# Zvukovuha2.net
KiCad netlist of a schematic drawn in EAGLE
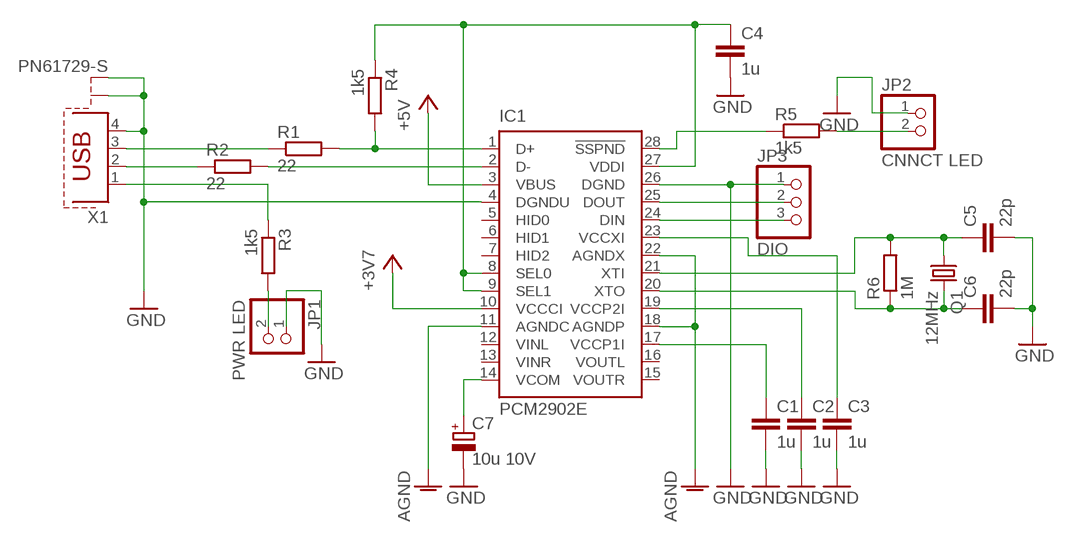
[diagram p0: schematic, sheet 1]

(export (version "E")
  (design (tool "Eeschema 10.0.6"))
  (components
    (comp (ref "C1")
      (value "1u")
      (footprint "eagle-import:C0805")
      (libsource (lib "eagle-import") (part "C-EUC0805"))
    )
    (comp (ref "C2")
      (value "1u")
      (footprint "eagle-import:C0805")
      (libsource (lib "eagle-import") (part "C-EUC0805"))
    )
    (comp (ref "C3")
      (value "1u")
      (footprint "eagle-import:C0805")
      (libsource (lib "eagle-import") (part "C-EUC0805"))
    )
    (comp (ref "C4")
      (value "1u")
      (footprint "eagle-import:C0805")
      (libsource (lib "eagle-import") (part "C-EUC0805"))
    )
    (comp (ref "C5")
      (value "22p")
      (footprint "eagle-import:C0805")
      (libsource (lib "eagle-import") (part "C-EUC0805"))
    )
    (comp (ref "C6")
      (value "22p")
      (footprint "eagle-import:C0805")
      (libsource (lib "eagle-import") (part "C-EUC0805"))
    )
    (comp (ref "C7")
      (value "10u 10V")
      (footprint "eagle-import:UD-6,3X7,7_NICHICON")
      (libsource (lib "eagle-import") (part "CPOL-EUUD-6,3X7,7"))
    )
    (comp (ref "IC1")
      (value "PCM2902E")
      (footprint "eagle-import:SSOP28DB")
      (fields (field (name "MF") "TEXAS INSTRUMENT CONNECTORS"))
      (libsource (lib "eagle-import") (part "PCM2902E"))
    )
    (comp (ref "JP1")
      (value "PWR LED")
      (footprint "eagle-import:1X02")
      (libsource (lib "eagle-import") (part "PINHD-1X2"))
    )
    (comp (ref "JP2")
      (value "CNNCT LED")
      (footprint "eagle-import:1X02")
      (libsource (lib "eagle-import") (part "PINHD-1X2"))
    )
    (comp (ref "JP3")
      (value "DIO")
      (footprint "eagle-import:1X03")
      (libsource (lib "eagle-import") (part "PINHD-1X3"))
    )
    (comp (ref "Q1")
      (value "12MHz")
      (footprint "eagle-import:CSM-7X-DU")
      (libsource (lib "eagle-import") (part "CSM-7X-DU"))
    )
    (comp (ref "R1")
      (value "22")
      (footprint "eagle-import:M1206")
      (libsource (lib "eagle-import") (part "R-EU_M1206"))
    )
    (comp (ref "R2")
      (value "22")
      (footprint "eagle-import:M1206")
      (libsource (lib "eagle-import") (part "R-EU_M1206"))
    )
    (comp (ref "R3")
      (value "1k5")
      (footprint "eagle-import:M1206")
      (libsource (lib "eagle-import") (part "R-EU_M1206"))
    )
    (comp (ref "R4")
      (value "1k5")
      (footprint "eagle-import:M1206")
      (libsource (lib "eagle-import") (part "R-EU_M1206"))
    )
    (comp (ref "R5")
      (value "1k5")
      (footprint "eagle-import:M1206")
      (libsource (lib "eagle-import") (part "R-EU_M1206"))
    )
    (comp (ref "R6")
      (value "1M")
      (footprint "eagle-import:M1206")
      (libsource (lib "eagle-import") (part "R-EU_M1206"))
    )
    (comp (ref "X1")
      (value "PN61729-S")
      (footprint "eagle-import:PN61729-S")
      (libsource (lib "eagle-import") (part "PN61729-S"))
    )
  )
  (nets
    (net (code "1") (name "+3V7") (class "Default")
      (node (ref "IC1") (pin "10") (pinfunction "VCCCI_10") (pintype "power_in"))
    )
    (net (code "2") (name "+5V") (class "Default")
      (node (ref "IC1") (pin "3") (pinfunction "VBUS_3") (pintype "power_in"))
    )
    (net (code "3") (name "AGND") (class "Default")
      (node (ref "IC1") (pin "11") (pinfunction "AGNDC_11") (pintype "power_in"))
      (node (ref "IC1") (pin "18") (pinfunction "AGNDP_18") (pintype "power_in"))
      (node (ref "IC1") (pin "22") (pinfunction "AGNDX_22") (pintype "power_in"))
    )
    (net (code "4") (name "GND") (class "Default")
      (node (ref "C1") (pin "2") (pinfunction "2_2") (pintype "passive"))
      (node (ref "C2") (pin "2") (pinfunction "2_2") (pintype "passive"))
      (node (ref "C3") (pin "2") (pinfunction "2_2") (pintype "passive"))
      (node (ref "C4") (pin "2") (pinfunction "2_2") (pintype "passive"))
      (node (ref "C5") (pin "2") (pinfunction "2_2") (pintype "passive"))
      (node (ref "C6") (pin "2") (pinfunction "2_2") (pintype "passive"))
      (node (ref "C7") (pin "-") (pinfunction "-_-") (pintype "passive"))
      (node (ref "IC1") (pin "26") (pinfunction "DGND_26") (pintype "power_in"))
      (node (ref "IC1") (pin "4") (pinfunction "DGNDU_4") (pintype "power_in"))
      (node (ref "JP1") (pin "1") (pinfunction "1_1") (pintype "passive"))
      (node (ref "JP2") (pin "1") (pinfunction "1_1") (pintype "passive"))
      (node (ref "JP3") (pin "1") (pinfunction "1_1") (pintype "passive"))
      (node (ref "X1") (pin "4") (pinfunction "4_4") (pintype "passive"))
      (node (ref "X1") (pin "S1") (pinfunction "S1_S1") (pintype "passive"))
      (node (ref "X1") (pin "S2") (pinfunction "S2_S2") (pintype "passive"))
    )
    (net (code "5") (name "Net-(IC1-D+)") (class "Default")
      (node (ref "IC1") (pin "1") (pinfunction "D+_1") (pintype "bidirectional"))
      (node (ref "R1") (pin "2") (pinfunction "2_2") (pintype "passive"))
      (node (ref "R4") (pin "2") (pinfunction "2_2") (pintype "passive"))
    )
    (net (code "6") (name "Net-(IC1-D-)") (class "Default")
      (node (ref "IC1") (pin "2") (pinfunction "D-_2") (pintype "bidirectional"))
      (node (ref "R2") (pin "2") (pinfunction "2_2") (pintype "passive"))
    )
    (net (code "7") (name "Net-(IC1-DIN)") (class "Default")
      (node (ref "IC1") (pin "24") (pinfunction "DIN_24") (pintype "input"))
      (node (ref "JP3") (pin "3") (pinfunction "3_3") (pintype "passive"))
    )
    (net (code "8") (name "Net-(IC1-DOUT)") (class "Default")
      (node (ref "IC1") (pin "25") (pinfunction "DOUT_25") (pintype "output"))
      (node (ref "JP3") (pin "2") (pinfunction "2_2") (pintype "passive"))
    )
    (net (code "9") (name "Net-(IC1-SEL0)") (class "Default")
      (node (ref "C4") (pin "1") (pinfunction "1_1") (pintype "passive"))
      (node (ref "IC1") (pin "27") (pinfunction "VDDI_27") (pintype "power_in"))
      (node (ref "IC1") (pin "8") (pinfunction "SEL0_8") (pintype "input"))
      (node (ref "IC1") (pin "9") (pinfunction "SEL1_9") (pintype "input"))
      (node (ref "R4") (pin "1") (pinfunction "1_1") (pintype "passive"))
    )
    (net (code "10") (name "Net-(IC1-VCCP1I)") (class "Default")
      (node (ref "C1") (pin "1") (pinfunction "1_1") (pintype "passive"))
      (node (ref "IC1") (pin "17") (pinfunction "VCCP1I_17") (pintype "input"))
    )
    (net (code "11") (name "Net-(IC1-VCCP2I)") (class "Default")
      (node (ref "C2") (pin "1") (pinfunction "1_1") (pintype "passive"))
      (node (ref "IC1") (pin "19") (pinfunction "VCCP2I_19") (pintype "power_in"))
    )
    (net (code "12") (name "Net-(IC1-VCCXI)") (class "Default")
      (node (ref "C3") (pin "1") (pinfunction "1_1") (pintype "passive"))
      (node (ref "IC1") (pin "23") (pinfunction "VCCXI_23") (pintype "power_in"))
    )
    (net (code "13") (name "Net-(IC1-VCOM)") (class "Default")
      (node (ref "C7") (pin "+") (pinfunction "+_+") (pintype "passive"))
      (node (ref "IC1") (pin "14") (pinfunction "VCOM_14") (pintype "power_in"))
    )
    (net (code "14") (name "Net-(IC1-XTI)") (class "Default")
      (node (ref "C5") (pin "1") (pinfunction "1_1") (pintype "passive"))
      (node (ref "IC1") (pin "21") (pinfunction "XTI_21") (pintype "input"))
      (node (ref "Q1") (pin "1") (pinfunction "1_1") (pintype "passive"))
      (node (ref "R6") (pin "2") (pinfunction "2_2") (pintype "passive"))
    )
    (net (code "15") (name "Net-(IC1-XTO)") (class "Default")
      (node (ref "C6") (pin "1") (pinfunction "1_1") (pintype "passive"))
      (node (ref "IC1") (pin "20") (pinfunction "XTO_20") (pintype "output"))
      (node (ref "Q1") (pin "2") (pinfunction "2_2") (pintype "passive"))
      (node (ref "R6") (pin "1") (pinfunction "1_1") (pintype "passive"))
    )
    (net (code "16") (name "Net-(IC1-~{SSPND})") (class "Default")
      (node (ref "IC1") (pin "28") (pinfunction "~{SSPND}_28") (pintype "output"))
      (node (ref "R5") (pin "1") (pinfunction "1_1") (pintype "passive"))
    )
    (net (code "17") (name "Net-(JP1-Pad2)") (class "Default")
      (node (ref "JP1") (pin "2") (pinfunction "2_2") (pintype "passive"))
      (node (ref "R3") (pin "2") (pinfunction "2_2") (pintype "passive"))
    )
    (net (code "18") (name "Net-(JP2-Pad2)") (class "Default")
      (node (ref "JP2") (pin "2") (pinfunction "2_2") (pintype "passive"))
      (node (ref "R5") (pin "2") (pinfunction "2_2") (pintype "passive"))
    )
    (net (code "19") (name "Net-(R1-Pad1)") (class "Default")
      (node (ref "R1") (pin "1") (pinfunction "1_1") (pintype "passive"))
      (node (ref "X1") (pin "3") (pinfunction "3_3") (pintype "passive"))
    )
    (net (code "20") (name "Net-(R2-Pad1)") (class "Default")
      (node (ref "R2") (pin "1") (pinfunction "1_1") (pintype "passive"))
      (node (ref "X1") (pin "2") (pinfunction "2_2") (pintype "passive"))
    )
    (net (code "21") (name "Net-(R3-Pad1)") (class "Default")
      (node (ref "R3") (pin "1") (pinfunction "1_1") (pintype "passive"))
      (node (ref "X1") (pin "1") (pinfunction "1_1") (pintype "passive"))
    )
    (net (code "22") (name "unconnected-(IC1-HID0-Pad5)") (class "Default")
      (node (ref "IC1") (pin "5") (pinfunction "HID0_5") (pintype "input"))
    )
    (net (code "23") (name "unconnected-(IC1-HID1-Pad6)") (class "Default")
      (node (ref "IC1") (pin "6") (pinfunction "HID1_6") (pintype "input"))
    )
    (net (code "24") (name "unconnected-(IC1-HID2-Pad7)") (class "Default")
      (node (ref "IC1") (pin "7") (pinfunction "HID2_7") (pintype "input"))
    )
    (net (code "25") (name "unconnected-(IC1-VINL-Pad12)") (class "Default")
      (node (ref "IC1") (pin "12") (pinfunction "VINL_12") (pintype "input"))
    )
    (net (code "26") (name "unconnected-(IC1-VINR-Pad13)") (class "Default")
      (node (ref "IC1") (pin "13") (pinfunction "VINR_13") (pintype "input"))
    )
    (net (code "27") (name "unconnected-(IC1-VOUTL-Pad16)") (class "Default")
      (node (ref "IC1") (pin "16") (pinfunction "VOUTL_16") (pintype "output"))
    )
    (net (code "28") (name "unconnected-(IC1-VOUTR-Pad15)") (class "Default")
      (node (ref "IC1") (pin "15") (pinfunction "VOUTR_15") (pintype "output"))
    )
  )
)
